# MB_STM32_VL.net
KiCad netlist of a schematic drawn in EAGLE
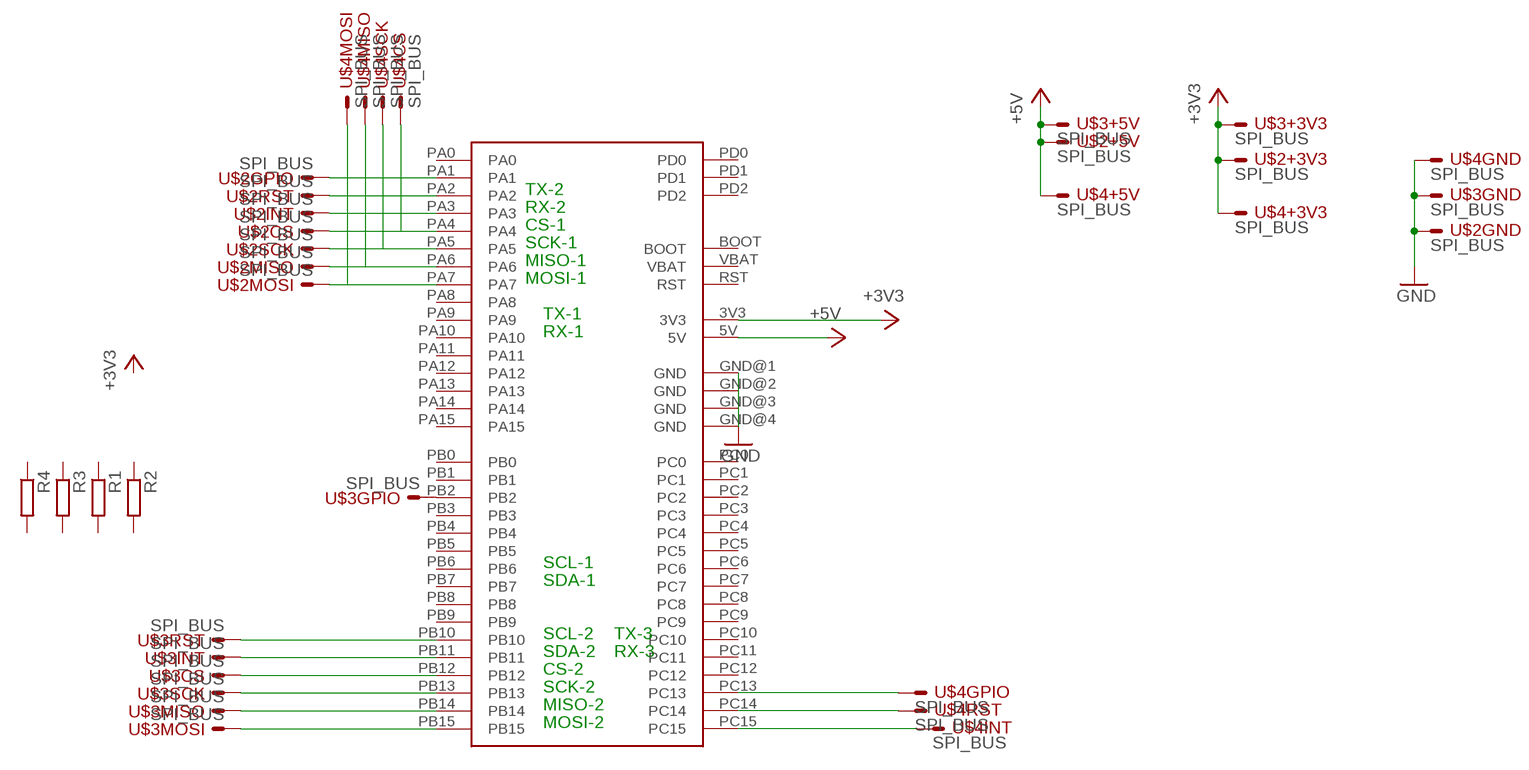
[diagram p0: schematic, sheet 1]

(export (version "E")
  (design (tool "Eeschema 10.0.6"))
  (components
    (comp (ref "R1")
      (value "R-EU_0204/7")
      (footprint "eagle-import:0204_7")
      (libsource (lib "eagle-import") (part "R-EU_0204/7"))
    )
    (comp (ref "R2")
      (value "R-EU_0204/7")
      (footprint "eagle-import:0204_7")
      (libsource (lib "eagle-import") (part "R-EU_0204/7"))
    )
    (comp (ref "R3")
      (value "R-EU_0204/7")
      (footprint "eagle-import:0204_7")
      (libsource (lib "eagle-import") (part "R-EU_0204/7"))
    )
    (comp (ref "R4")
      (value "R-EU_0204/7")
      (footprint "eagle-import:0204_7")
      (libsource (lib "eagle-import") (part "R-EU_0204/7"))
    )
    (comp (ref "U$1")
      (value "STM32_DISCOVERY")
      (footprint "eagle-import:STM32_DISCOVERY")
      (libsource (lib "eagle-import") (part "STM32_DISCOVERY"))
    )
    (comp (ref "U$2")
      (value "SPI_BUS")
      (footprint "eagle-import:SPI_BUS")
      (libsource (lib "eagle-import") (part "SPI_BUS"))
    )
    (comp (ref "U$3")
      (value "SPI_BUS")
      (footprint "eagle-import:SPI_BUS")
      (libsource (lib "eagle-import") (part "SPI_BUS"))
    )
    (comp (ref "U$4")
      (value "SPI_BUS")
      (footprint "eagle-import:SPI_BUS")
      (libsource (lib "eagle-import") (part "SPI_BUS"))
    )
  )
  (nets
    (net (code "1") (name "+3V3") (class "Default")
      (node (ref "U$1") (pin "3V3") (pinfunction "3V3_3V3") (pintype "bidirectional"))
      (node (ref "U$2") (pin "+3V3") (pinfunction "S_+3V3") (pintype "passive"))
      (node (ref "U$3") (pin "+3V3") (pinfunction "S_+3V3") (pintype "passive"))
      (node (ref "U$4") (pin "+3V3") (pinfunction "S_+3V3") (pintype "passive"))
    )
    (net (code "2") (name "+5V") (class "Default")
      (node (ref "U$1") (pin "5V") (pinfunction "5V_5V") (pintype "bidirectional"))
      (node (ref "U$2") (pin "+5V") (pinfunction "S_+5V") (pintype "passive"))
      (node (ref "U$3") (pin "+5V") (pinfunction "S_+5V") (pintype "passive"))
      (node (ref "U$4") (pin "+5V") (pinfunction "S_+5V") (pintype "passive"))
    )
    (net (code "3") (name "GND") (class "Default")
      (node (ref "U$1") (pin "GND@1") (pinfunction "GND_GND@1") (pintype "bidirectional"))
      (node (ref "U$1") (pin "GND@2") (pinfunction "GND_GND@2") (pintype "bidirectional"))
      (node (ref "U$1") (pin "GND@3") (pinfunction "GND_GND@3") (pintype "bidirectional"))
      (node (ref "U$1") (pin "GND@4") (pinfunction "GND_GND@4") (pintype "bidirectional"))
      (node (ref "U$2") (pin "GND") (pinfunction "S_GND") (pintype "passive"))
      (node (ref "U$3") (pin "GND") (pinfunction "S_GND") (pintype "passive"))
      (node (ref "U$4") (pin "GND") (pinfunction "S_GND") (pintype "passive"))
    )
    (net (code "4") (name "Net-(U$2C-S)") (class "Default")
      (node (ref "U$1") (pin "PA4") (pinfunction "PA4_PA4") (pintype "bidirectional"))
      (node (ref "U$2") (pin "CS") (pinfunction "S_CS") (pintype "passive"))
      (node (ref "U$4") (pin "CS") (pinfunction "S_CS") (pintype "passive"))
    )
    (net (code "5") (name "Net-(U$2E-S)") (class "Default")
      (node (ref "U$1") (pin "PA1") (pinfunction "PA1_PA1") (pintype "bidirectional"))
      (node (ref "U$2") (pin "GPIO") (pinfunction "S_GPIO") (pintype "passive"))
    )
    (net (code "6") (name "Net-(U$2F-S)") (class "Default")
      (node (ref "U$1") (pin "PA3") (pinfunction "PA3_PA3") (pintype "bidirectional"))
      (node (ref "U$2") (pin "INT") (pinfunction "S_INT") (pintype "passive"))
    )
    (net (code "7") (name "Net-(U$2G-S)") (class "Default")
      (node (ref "U$1") (pin "PA6") (pinfunction "PA6_PA6") (pintype "bidirectional"))
      (node (ref "U$2") (pin "MISO") (pinfunction "S_MISO") (pintype "passive"))
      (node (ref "U$4") (pin "MISO") (pinfunction "S_MISO") (pintype "passive"))
    )
    (net (code "8") (name "Net-(U$2H-S)") (class "Default")
      (node (ref "U$1") (pin "PA7") (pinfunction "PA7_PA7") (pintype "bidirectional"))
      (node (ref "U$2") (pin "MOSI") (pinfunction "S_MOSI") (pintype "passive"))
      (node (ref "U$4") (pin "MOSI") (pinfunction "S_MOSI") (pintype "passive"))
    )
    (net (code "9") (name "Net-(U$2I-S)") (class "Default")
      (node (ref "U$1") (pin "PA2") (pinfunction "PA2_PA2") (pintype "bidirectional"))
      (node (ref "U$2") (pin "RST") (pinfunction "S_RST") (pintype "passive"))
    )
    (net (code "10") (name "Net-(U$2J-S)") (class "Default")
      (node (ref "U$1") (pin "PA5") (pinfunction "PA5_PA5") (pintype "bidirectional"))
      (node (ref "U$2") (pin "SCK") (pinfunction "S_SCK") (pintype "passive"))
      (node (ref "U$4") (pin "SCK") (pinfunction "S_SCK") (pintype "passive"))
    )
    (net (code "11") (name "Net-(U$3C-S)") (class "Default")
      (node (ref "U$1") (pin "PB12") (pinfunction "PB12_PB12") (pintype "bidirectional"))
      (node (ref "U$3") (pin "CS") (pinfunction "S_CS") (pintype "passive"))
    )
    (net (code "12") (name "Net-(U$3E-S)") (class "Default")
      (node (ref "U$1") (pin "PB2") (pinfunction "PB2_PB2") (pintype "bidirectional"))
      (node (ref "U$3") (pin "GPIO") (pinfunction "S_GPIO") (pintype "passive"))
    )
    (net (code "13") (name "Net-(U$3F-S)") (class "Default")
      (node (ref "U$1") (pin "PB11") (pinfunction "PB11_PB11") (pintype "bidirectional"))
      (node (ref "U$3") (pin "INT") (pinfunction "S_INT") (pintype "passive"))
    )
    (net (code "14") (name "Net-(U$3G-S)") (class "Default")
      (node (ref "U$1") (pin "PB14") (pinfunction "PB14_PB14") (pintype "bidirectional"))
      (node (ref "U$3") (pin "MISO") (pinfunction "S_MISO") (pintype "passive"))
    )
    (net (code "15") (name "Net-(U$3H-S)") (class "Default")
      (node (ref "U$1") (pin "PB15") (pinfunction "PB15_PB15") (pintype "bidirectional"))
      (node (ref "U$3") (pin "MOSI") (pinfunction "S_MOSI") (pintype "passive"))
    )
    (net (code "16") (name "Net-(U$3I-S)") (class "Default")
      (node (ref "U$1") (pin "PB10") (pinfunction "PB10_PB10") (pintype "bidirectional"))
      (node (ref "U$3") (pin "RST") (pinfunction "S_RST") (pintype "passive"))
    )
    (net (code "17") (name "Net-(U$3J-S)") (class "Default")
      (node (ref "U$1") (pin "PB13") (pinfunction "PB13_PB13") (pintype "bidirectional"))
      (node (ref "U$3") (pin "SCK") (pinfunction "S_SCK") (pintype "passive"))
    )
    (net (code "18") (name "Net-(U$4E-S)") (class "Default")
      (node (ref "U$1") (pin "PC13") (pinfunction "PC13_PC13") (pintype "bidirectional"))
      (node (ref "U$4") (pin "GPIO") (pinfunction "S_GPIO") (pintype "passive"))
    )
    (net (code "19") (name "Net-(U$4F-S)") (class "Default")
      (node (ref "U$1") (pin "PC15") (pinfunction "PC15_PC15") (pintype "bidirectional"))
      (node (ref "U$4") (pin "INT") (pinfunction "S_INT") (pintype "passive"))
    )
    (net (code "20") (name "Net-(U$4I-S)") (class "Default")
      (node (ref "U$1") (pin "PC14") (pinfunction "PC14_PC14") (pintype "bidirectional"))
      (node (ref "U$4") (pin "RST") (pinfunction "S_RST") (pintype "passive"))
    )
    (net (code "21") (name "unconnected-(R1-Pad1)") (class "Default")
      (node (ref "R1") (pin "1") (pinfunction "1_1") (pintype "passive"))
    )
    (net (code "22") (name "unconnected-(R1-Pad2)") (class "Default")
      (node (ref "R1") (pin "2") (pinfunction "2_2") (pintype "passive"))
    )
    (net (code "23") (name "unconnected-(R2-Pad1)") (class "Default")
      (node (ref "R2") (pin "1") (pinfunction "1_1") (pintype "passive"))
    )
    (net (code "24") (name "unconnected-(R2-Pad2)") (class "Default")
      (node (ref "R2") (pin "2") (pinfunction "2_2") (pintype "passive"))
    )
    (net (code "25") (name "unconnected-(R3-Pad1)") (class "Default")
      (node (ref "R3") (pin "1") (pinfunction "1_1") (pintype "passive"))
    )
    (net (code "26") (name "unconnected-(R3-Pad2)") (class "Default")
      (node (ref "R3") (pin "2") (pinfunction "2_2") (pintype "passive"))
    )
    (net (code "27") (name "unconnected-(R4-Pad1)") (class "Default")
      (node (ref "R4") (pin "1") (pinfunction "1_1") (pintype "passive"))
    )
    (net (code "28") (name "unconnected-(R4-Pad2)") (class "Default")
      (node (ref "R4") (pin "2") (pinfunction "2_2") (pintype "passive"))
    )
    (net (code "29") (name "unconnected-(U$1-NC-PadNC@1)") (class "Default")
      (node (ref "U$1") (pin "NC@1") (pinfunction "NC_NC@1") (pintype "bidirectional"))
    )
    (net (code "30") (name "unconnected-(U$1-NC-PadNC@2)") (class "Default")
      (node (ref "U$1") (pin "NC@2") (pinfunction "NC_NC@2") (pintype "bidirectional"))
    )
    (net (code "31") (name "unconnected-(U$1-PadBOOT)") (class "Default")
      (node (ref "U$1") (pin "BOOT") (pinfunction "BOOT_BOOT") (pintype "bidirectional"))
    )
    (net (code "32") (name "unconnected-(U$1-PadPA0)") (class "Default")
      (node (ref "U$1") (pin "PA0") (pinfunction "PA0_PA0") (pintype "bidirectional"))
    )
    (net (code "33") (name "unconnected-(U$1-PadPA8)") (class "Default")
      (node (ref "U$1") (pin "PA8") (pinfunction "PA8_PA8") (pintype "bidirectional"))
    )
    (net (code "34") (name "unconnected-(U$1-PadPA9)") (class "Default")
      (node (ref "U$1") (pin "PA9") (pinfunction "PA9_PA9") (pintype "bidirectional"))
    )
    (net (code "35") (name "unconnected-(U$1-PadPA10)") (class "Default")
      (node (ref "U$1") (pin "PA10") (pinfunction "PA10_PA10") (pintype "bidirectional"))
    )
    (net (code "36") (name "unconnected-(U$1-PadPA11)") (class "Default")
      (node (ref "U$1") (pin "PA11") (pinfunction "PA11_PA11") (pintype "bidirectional"))
    )
    (net (code "37") (name "unconnected-(U$1-PadPA12)") (class "Default")
      (node (ref "U$1") (pin "PA12") (pinfunction "PA12_PA12") (pintype "bidirectional"))
    )
    (net (code "38") (name "unconnected-(U$1-PadPA13)") (class "Default")
      (node (ref "U$1") (pin "PA13") (pinfunction "PA13_PA13") (pintype "bidirectional"))
    )
    (net (code "39") (name "unconnected-(U$1-PadPA14)") (class "Default")
      (node (ref "U$1") (pin "PA14") (pinfunction "PA14_PA14") (pintype "bidirectional"))
    )
    (net (code "40") (name "unconnected-(U$1-PadPA15)") (class "Default")
      (node (ref "U$1") (pin "PA15") (pinfunction "PA15_PA15") (pintype "bidirectional"))
    )
    (net (code "41") (name "unconnected-(U$1-PadPB0)") (class "Default")
      (node (ref "U$1") (pin "PB0") (pinfunction "PB0_PB0") (pintype "bidirectional"))
    )
    (net (code "42") (name "unconnected-(U$1-PadPB1)") (class "Default")
      (node (ref "U$1") (pin "PB1") (pinfunction "PB1_PB1") (pintype "bidirectional"))
    )
    (net (code "43") (name "unconnected-(U$1-PadPB3)") (class "Default")
      (node (ref "U$1") (pin "PB3") (pinfunction "PB3_PB3") (pintype "bidirectional"))
    )
    (net (code "44") (name "unconnected-(U$1-PadPB4)") (class "Default")
      (node (ref "U$1") (pin "PB4") (pinfunction "PB4_PB4") (pintype "bidirectional"))
    )
    (net (code "45") (name "unconnected-(U$1-PadPB5)") (class "Default")
      (node (ref "U$1") (pin "PB5") (pinfunction "PB5_PB5") (pintype "bidirectional"))
    )
    (net (code "46") (name "unconnected-(U$1-PadPB6)") (class "Default")
      (node (ref "U$1") (pin "PB6") (pinfunction "PB6_PB6") (pintype "bidirectional"))
    )
    (net (code "47") (name "unconnected-(U$1-PadPB7)") (class "Default")
      (node (ref "U$1") (pin "PB7") (pinfunction "PB7_PB7") (pintype "bidirectional"))
    )
    (net (code "48") (name "unconnected-(U$1-PadPB8)") (class "Default")
      (node (ref "U$1") (pin "PB8") (pinfunction "PB8_PB8") (pintype "bidirectional"))
    )
    (net (code "49") (name "unconnected-(U$1-PadPB9)") (class "Default")
      (node (ref "U$1") (pin "PB9") (pinfunction "PB9_PB9") (pintype "bidirectional"))
    )
    (net (code "50") (name "unconnected-(U$1-PadPC0)") (class "Default")
      (node (ref "U$1") (pin "PC0") (pinfunction "PC0_PC0") (pintype "bidirectional"))
    )
    (net (code "51") (name "unconnected-(U$1-PadPC1)") (class "Default")
      (node (ref "U$1") (pin "PC1") (pinfunction "PC1_PC1") (pintype "bidirectional"))
    )
    (net (code "52") (name "unconnected-(U$1-PadPC2)") (class "Default")
      (node (ref "U$1") (pin "PC2") (pinfunction "PC2_PC2") (pintype "bidirectional"))
    )
    (net (code "53") (name "unconnected-(U$1-PadPC3)") (class "Default")
      (node (ref "U$1") (pin "PC3") (pinfunction "PC3_PC3") (pintype "bidirectional"))
    )
    (net (code "54") (name "unconnected-(U$1-PadPC4)") (class "Default")
      (node (ref "U$1") (pin "PC4") (pinfunction "PC4_PC4") (pintype "bidirectional"))
    )
    (net (code "55") (name "unconnected-(U$1-PadPC5)") (class "Default")
      (node (ref "U$1") (pin "PC5") (pinfunction "PC5_PC5") (pintype "bidirectional"))
    )
    (net (code "56") (name "unconnected-(U$1-PadPC6)") (class "Default")
      (node (ref "U$1") (pin "PC6") (pinfunction "PC6_PC6") (pintype "bidirectional"))
    )
    (net (code "57") (name "unconnected-(U$1-PadPC7)") (class "Default")
      (node (ref "U$1") (pin "PC7") (pinfunction "PC7_PC7") (pintype "bidirectional"))
    )
    (net (code "58") (name "unconnected-(U$1-PadPC8)") (class "Default")
      (node (ref "U$1") (pin "PC8") (pinfunction "PC8_PC8") (pintype "bidirectional"))
    )
    (net (code "59") (name "unconnected-(U$1-PadPC9)") (class "Default")
      (node (ref "U$1") (pin "PC9") (pinfunction "PC9_PC9") (pintype "bidirectional"))
    )
    (net (code "60") (name "unconnected-(U$1-PadPC10)") (class "Default")
      (node (ref "U$1") (pin "PC10") (pinfunction "PC10_PC10") (pintype "bidirectional"))
    )
    (net (code "61") (name "unconnected-(U$1-PadPC11)") (class "Default")
      (node (ref "U$1") (pin "PC11") (pinfunction "PC11_PC11") (pintype "bidirectional"))
    )
    (net (code "62") (name "unconnected-(U$1-PadPC12)") (class "Default")
      (node (ref "U$1") (pin "PC12") (pinfunction "PC12_PC12") (pintype "bidirectional"))
    )
    (net (code "63") (name "unconnected-(U$1-PadPD0)") (class "Default")
      (node (ref "U$1") (pin "PD0") (pinfunction "PD0_PD0") (pintype "bidirectional"))
    )
    (net (code "64") (name "unconnected-(U$1-PadPD1)") (class "Default")
      (node (ref "U$1") (pin "PD1") (pinfunction "PD1_PD1") (pintype "bidirectional"))
    )
    (net (code "65") (name "unconnected-(U$1-PadPD2)") (class "Default")
      (node (ref "U$1") (pin "PD2") (pinfunction "PD2_PD2") (pintype "bidirectional"))
    )
    (net (code "66") (name "unconnected-(U$1-PadRST)") (class "Default")
      (node (ref "U$1") (pin "RST") (pinfunction "RST_RST") (pintype "bidirectional"))
    )
    (net (code "67") (name "unconnected-(U$1-PadVBAT)") (class "Default")
      (node (ref "U$1") (pin "VBAT") (pinfunction "VBAT_VBAT") (pintype "bidirectional"))
    )
  )
)
